# xduino360.net
KiCad netlist of a schematic drawn in EAGLE
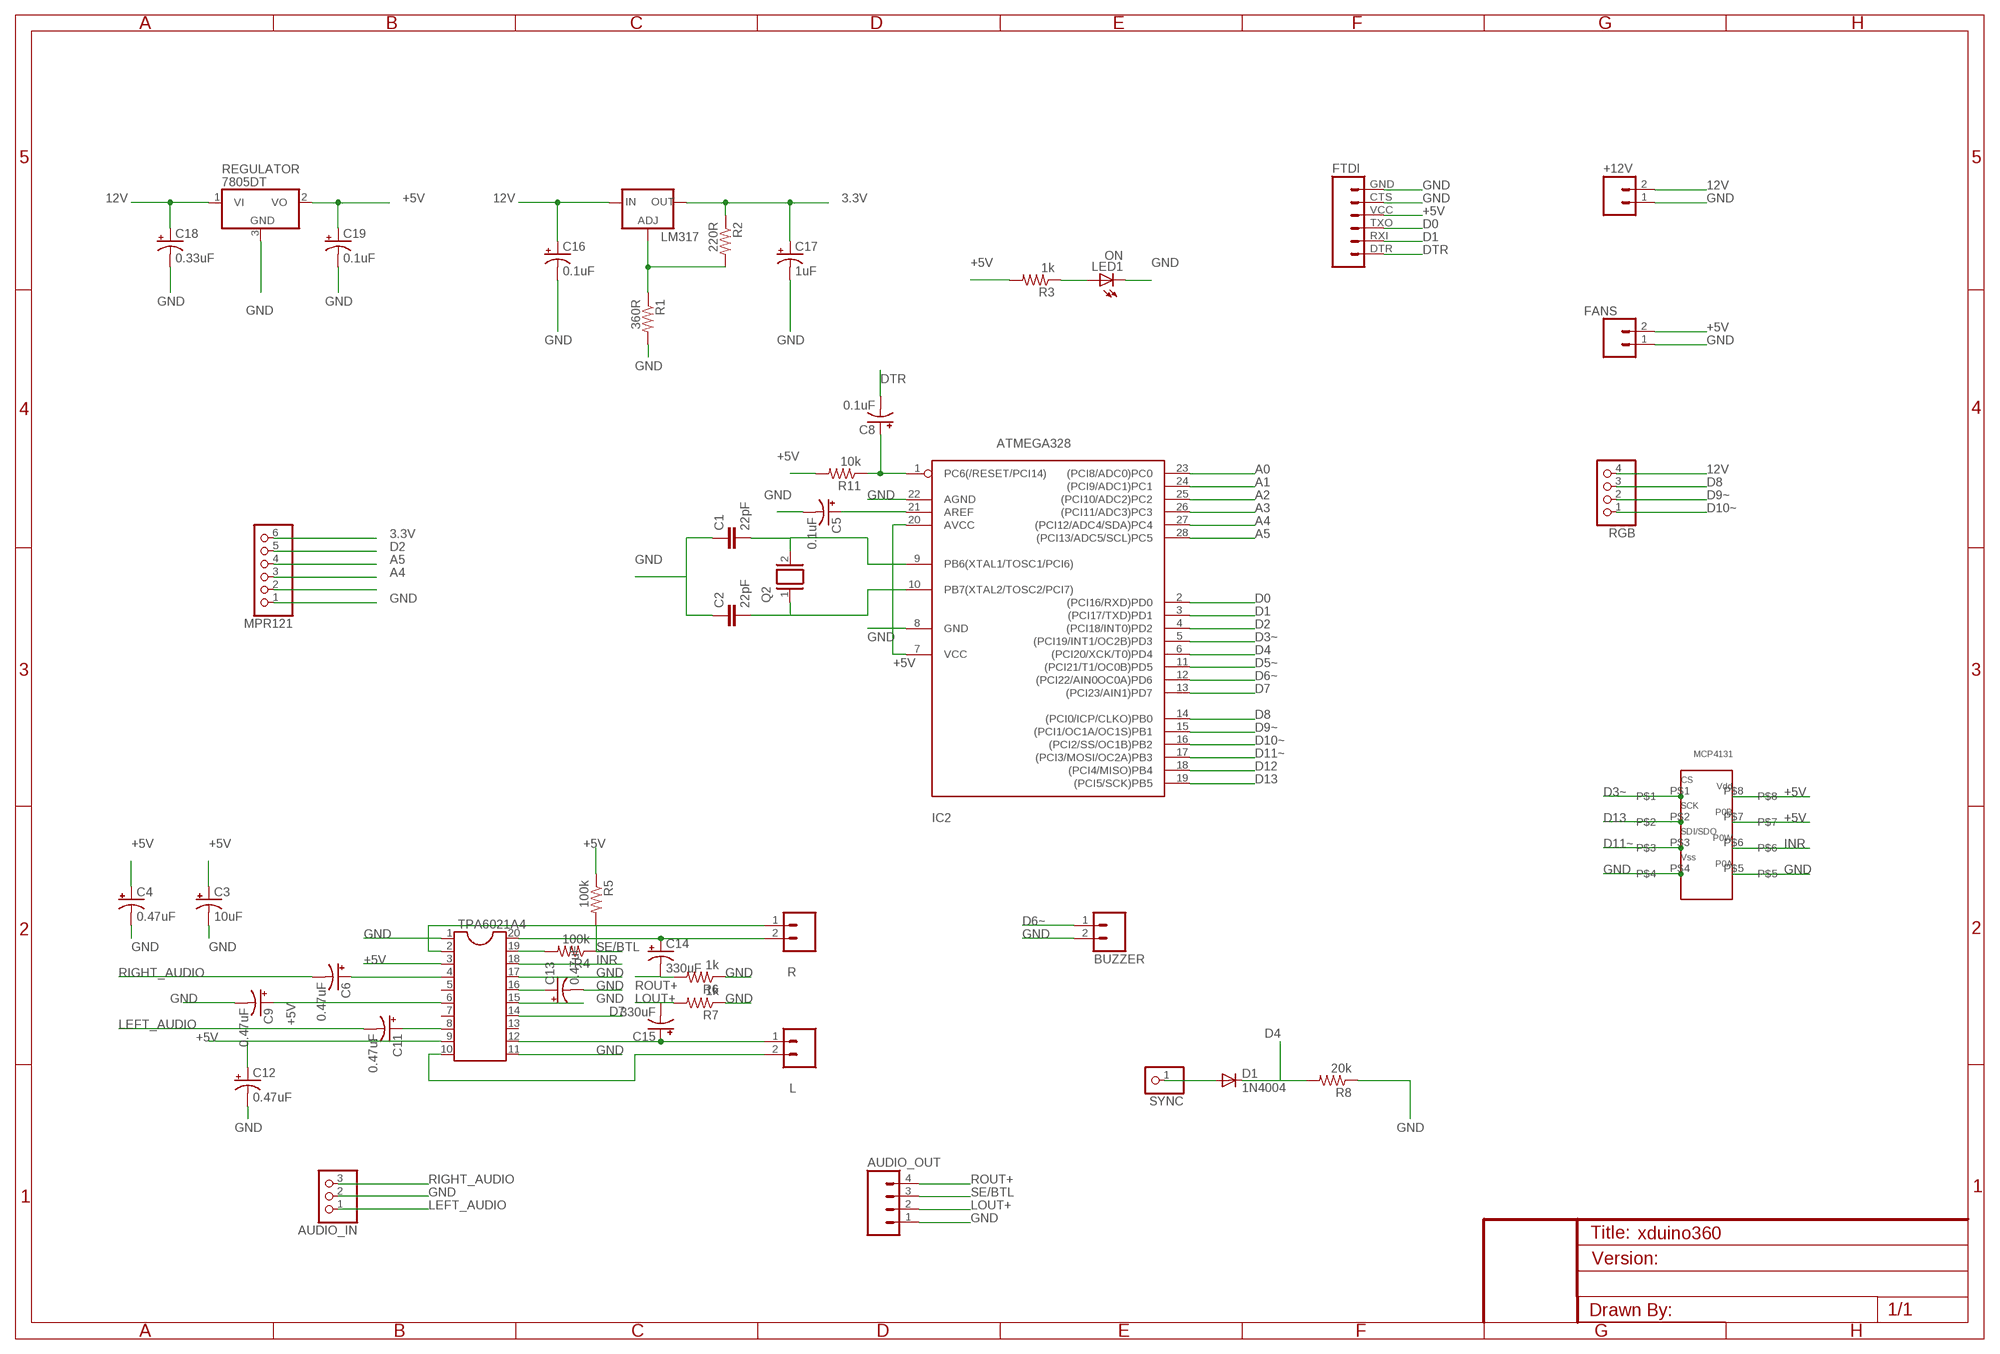
[diagram p0: schematic, sheet 1]

(export (version "E")
  (design (tool "Eeschema 10.0.6"))
  (components
    (comp (ref "+12V")
      (value "M02PTH")
      (footprint "eagle-import:1X02")
      (libsource (lib "eagle-import") (part "M02PTH"))
    )
    (comp (ref "AUDIO_IN")
      (value "PINHD-1X3")
      (footprint "eagle-import:1X03")
      (libsource (lib "eagle-import") (part "PINHD-1X3"))
    )
    (comp (ref "AUDIO_OUT")
      (value "M04PTH")
      (footprint "eagle-import:1X04")
      (libsource (lib "eagle-import") (part "M04PTH"))
    )
    (comp (ref "BUZZER")
      (value "M02PTH")
      (footprint "eagle-import:1X02")
      (libsource (lib "eagle-import") (part "M02PTH"))
    )
    (comp (ref "C1")
      (value "22pF")
      (footprint "eagle-import:C5B2.5")
      (libsource (lib "eagle-import") (part "C5/2.5"))
    )
    (comp (ref "C2")
      (value "22pF")
      (footprint "eagle-import:C5B2.5")
      (libsource (lib "eagle-import") (part "C5/2.5"))
    )
    (comp (ref "C3")
      (value "10uF")
      (footprint "eagle-import:TT2D5")
      (libsource (lib "eagle-import") (part "CPOL-USTT2D5"))
    )
    (comp (ref "C4")
      (value "0.47uF")
      (footprint "eagle-import:TT2D5")
      (libsource (lib "eagle-import") (part "CPOL-USTT2D5"))
    )
    (comp (ref "C5")
      (value "0.1uF")
      (footprint "eagle-import:TT2D5")
      (libsource (lib "eagle-import") (part "CPOL-USTT2D5"))
    )
    (comp (ref "C6")
      (value "0.47uF")
      (footprint "eagle-import:TT2D5")
      (libsource (lib "eagle-import") (part "CPOL-USTT2D5"))
    )
    (comp (ref "C8")
      (value "0.1uF")
      (footprint "eagle-import:TT2D5")
      (libsource (lib "eagle-import") (part "CPOL-USTT2D5"))
    )
    (comp (ref "C9")
      (value "0.47uF")
      (footprint "eagle-import:TT2D5")
      (libsource (lib "eagle-import") (part "CPOL-USTT2D5"))
    )
    (comp (ref "C11")
      (value "0.47uF")
      (footprint "eagle-import:TT2D5")
      (libsource (lib "eagle-import") (part "CPOL-USTT2D5"))
    )
    (comp (ref "C12")
      (value "0.47uF")
      (footprint "eagle-import:TT2D5")
      (libsource (lib "eagle-import") (part "CPOL-USTT2D5"))
    )
    (comp (ref "C13")
      (value "0.47uF")
      (footprint "eagle-import:TT2D5")
      (libsource (lib "eagle-import") (part "CPOL-USTT2D5"))
    )
    (comp (ref "C14")
      (value "330uF")
      (footprint "eagle-import:TT2D5")
      (libsource (lib "eagle-import") (part "CPOL-USTT2D5"))
    )
    (comp (ref "C15")
      (value "330uF")
      (footprint "eagle-import:TT2D5")
      (libsource (lib "eagle-import") (part "CPOL-USTT2D5"))
    )
    (comp (ref "C16")
      (value "0.1uF")
      (footprint "eagle-import:TT2D5")
      (libsource (lib "eagle-import") (part "CPOL-USTT2D5"))
    )
    (comp (ref "C17")
      (value "1uF")
      (footprint "eagle-import:TT2D5")
      (libsource (lib "eagle-import") (part "CPOL-USTT2D5"))
    )
    (comp (ref "C18")
      (value "0.33uF")
      (footprint "eagle-import:TT2D5")
      (libsource (lib "eagle-import") (part "CPOL-USTT2D5"))
    )
    (comp (ref "C19")
      (value "0.1uF")
      (footprint "eagle-import:TT2D5")
      (libsource (lib "eagle-import") (part "CPOL-USTT2D5"))
    )
    (comp (ref "D1")
      (value "1N4004")
      (footprint "eagle-import:DO41-10")
      (libsource (lib "eagle-import") (part "1N4004"))
    )
    (comp (ref "FANS")
      (value "M02PTH")
      (footprint "eagle-import:1X02")
      (libsource (lib "eagle-import") (part "M02PTH"))
    )
    (comp (ref "FTDI")
      (value "FTDI_BASICPTH")
      (footprint "eagle-import:FTDI_BASIC")
      (libsource (lib "eagle-import") (part "FTDI_BASICPTH"))
    )
    (comp (ref "IC2")
      (value "ATMEGA328")
      (footprint "eagle-import:DIL28-3")
      (libsource (lib "eagle-import") (part "ATMEGA168PV-10"))
    )
    (comp (ref "L")
      (value "M02PTH")
      (footprint "eagle-import:1X02")
      (libsource (lib "eagle-import") (part "M02PTH"))
    )
    (comp (ref "LED1")
      (value "ON")
      (footprint "eagle-import:LED3MM")
      (libsource (lib "eagle-import") (part "LED3MM"))
    )
    (comp (ref "LM317")
      (value "V_REG_317DPACK")
      (footprint "eagle-import:V-REG_DPACK")
      (libsource (lib "eagle-import") (part "V_REG_317DPACK"))
    )
    (comp (ref "MCP4131")
      (value "MCP4131")
      (footprint "eagle-import:MCP4131")
      (libsource (lib "eagle-import") (part "MCP4131"))
    )
    (comp (ref "MPR121")
      (value "PINHD-1X6")
      (footprint "eagle-import:1X06")
      (libsource (lib "eagle-import") (part "PINHD-1X6"))
    )
    (comp (ref "Q2")
      (value "XTAL/S")
      (footprint "eagle-import:QS")
      (libsource (lib "eagle-import") (part "XTAL/S"))
    )
    (comp (ref "R")
      (value "M02PTH")
      (footprint "eagle-import:1X02")
      (libsource (lib "eagle-import") (part "M02PTH"))
    )
    (comp (ref "R1")
      (value "360R")
      (footprint "eagle-import:0204V")
      (libsource (lib "eagle-import") (part "R-US_0204/2V"))
    )
    (comp (ref "R2")
      (value "220R")
      (footprint "eagle-import:0204V")
      (libsource (lib "eagle-import") (part "R-US_0204/2V"))
    )
    (comp (ref "R3")
      (value "1k")
      (footprint "eagle-import:0204V")
      (libsource (lib "eagle-import") (part "R-US_0204/2V"))
    )
    (comp (ref "R4")
      (value "100k")
      (footprint "eagle-import:0204V")
      (libsource (lib "eagle-import") (part "R-US_0204/2V"))
    )
    (comp (ref "R5")
      (value "100k")
      (footprint "eagle-import:0204V")
      (libsource (lib "eagle-import") (part "R-US_0204/2V"))
    )
    (comp (ref "R6")
      (value "1k")
      (footprint "eagle-import:0204V")
      (libsource (lib "eagle-import") (part "R-US_0204/2V"))
    )
    (comp (ref "R7")
      (value "1k")
      (footprint "eagle-import:0204V")
      (libsource (lib "eagle-import") (part "R-US_0204/2V"))
    )
    (comp (ref "R8")
      (value "20k")
      (footprint "eagle-import:0204V")
      (libsource (lib "eagle-import") (part "R-US_0204/2V"))
    )
    (comp (ref "R11")
      (value "10k")
      (footprint "eagle-import:0204V")
      (libsource (lib "eagle-import") (part "R-US_0204/2V"))
    )
    (comp (ref "REGULATOR")
      (value "7805DT")
      (footprint "eagle-import:TO252")
      (libsource (lib "eagle-import") (part "78DT05"))
    )
    (comp (ref "RGB")
      (value "PINHD-1X4")
      (footprint "eagle-import:1X04")
      (libsource (lib "eagle-import") (part "PINHD-1X4"))
    )
    (comp (ref "SYNC")
      (value "PINHD-1X1")
      (footprint "eagle-import:1X01")
      (libsource (lib "eagle-import") (part "PINHD-1X1"))
    )
    (comp (ref "TPA6021A4")
      (value "DIL20")
      (footprint "eagle-import:DIL20")
      (libsource (lib "eagle-import") (part "DIL20"))
    )
  )
  (nets
    (net (code "1") (name "/+5V") (class "Default")
      (node (ref "C12") (pin "+") (pinfunction "+_+") (pintype "passive"))
      (node (ref "C19") (pin "+") (pinfunction "+_+") (pintype "passive"))
      (node (ref "C3") (pin "+") (pinfunction "+_+") (pintype "passive"))
      (node (ref "C4") (pin "+") (pinfunction "+_+") (pintype "passive"))
      (node (ref "C9") (pin "+") (pinfunction "+_+") (pintype "passive"))
      (node (ref "FANS") (pin "2") (pinfunction "2_2") (pintype "passive"))
      (node (ref "FTDI") (pin "VCC") (pinfunction "4_VCC") (pintype "passive"))
      (node (ref "IC2") (pin "20") (pinfunction "AVCC_20") (pintype "bidirectional"))
      (node (ref "IC2") (pin "7") (pinfunction "VCC_7") (pintype "bidirectional"))
      (node (ref "MCP4131") (pin "P$7") (pinfunction "P$7_P$7") (pintype "bidirectional"))
      (node (ref "MCP4131") (pin "P$8") (pinfunction "P$8_P$8") (pintype "bidirectional"))
      (node (ref "R11") (pin "2") (pinfunction "2_2") (pintype "passive"))
      (node (ref "R3") (pin "2") (pinfunction "2_2") (pintype "passive"))
      (node (ref "R5") (pin "1") (pinfunction "1_1") (pintype "passive"))
      (node (ref "REGULATOR") (pin "2") (pinfunction "VO_2") (pintype "passive"))
      (node (ref "TPA6021A4") (pin "3") (pinfunction "3_3") (pintype "passive"))
      (node (ref "TPA6021A4") (pin "6") (pinfunction "6_6") (pintype "passive"))
      (node (ref "TPA6021A4") (pin "9") (pinfunction "9_9") (pintype "passive"))
    )
    (net (code "2") (name "/3.3V") (class "Default")
      (node (ref "C17") (pin "+") (pinfunction "+_+") (pintype "passive"))
      (node (ref "LM317") (pin "4") (pinfunction "OUT_4") (pintype "output"))
      (node (ref "MPR121") (pin "6") (pinfunction "6_6") (pintype "passive"))
      (node (ref "R2") (pin "1") (pinfunction "1_1") (pintype "passive"))
    )
    (net (code "3") (name "/12V") (class "Default")
      (node (ref "+12V") (pin "2") (pinfunction "2_2") (pintype "passive"))
      (node (ref "C16") (pin "+") (pinfunction "+_+") (pintype "passive"))
      (node (ref "C18") (pin "+") (pinfunction "+_+") (pintype "passive"))
      (node (ref "LM317") (pin "3") (pinfunction "IN_3") (pintype "input"))
      (node (ref "REGULATOR") (pin "1") (pinfunction "VI_1") (pintype "input"))
      (node (ref "RGB") (pin "4") (pinfunction "4_4") (pintype "passive"))
    )
    (net (code "4") (name "/A0") (class "Default")
      (node (ref "IC2") (pin "23") (pinfunction "(PCI8/ADC0)PC0_23") (pintype "bidirectional"))
    )
    (net (code "5") (name "/A1") (class "Default")
      (node (ref "IC2") (pin "24") (pinfunction "(PCI9/ADC1)PC1_24") (pintype "bidirectional"))
    )
    (net (code "6") (name "/A2") (class "Default")
      (node (ref "IC2") (pin "25") (pinfunction "(PCI10/ADC2)PC2_25") (pintype "bidirectional"))
    )
    (net (code "7") (name "/A3") (class "Default")
      (node (ref "IC2") (pin "26") (pinfunction "(PCI11/ADC3)PC3_26") (pintype "bidirectional"))
    )
    (net (code "8") (name "/A4") (class "Default")
      (node (ref "IC2") (pin "27") (pinfunction "(PCI12/ADC4/SDA)PC4_27") (pintype "bidirectional"))
      (node (ref "MPR121") (pin "3") (pinfunction "3_3") (pintype "passive"))
    )
    (net (code "9") (name "/A5") (class "Default")
      (node (ref "IC2") (pin "28") (pinfunction "(PCI13/ADC5/SCL)PC5_28") (pintype "bidirectional"))
      (node (ref "MPR121") (pin "4") (pinfunction "4_4") (pintype "passive"))
    )
    (net (code "10") (name "/D0") (class "Default")
      (node (ref "FTDI") (pin "TXO") (pinfunction "3_TXO") (pintype "passive"))
      (node (ref "IC2") (pin "2") (pinfunction "(PCI16/RXD)PD0_2") (pintype "bidirectional"))
    )
    (net (code "11") (name "/D1") (class "Default")
      (node (ref "FTDI") (pin "RXI") (pinfunction "2_RXI") (pintype "passive"))
      (node (ref "IC2") (pin "3") (pinfunction "(PCI17/TXD)PD1_3") (pintype "bidirectional"))
    )
    (net (code "12") (name "/D2") (class "Default")
      (node (ref "IC2") (pin "4") (pinfunction "(PCI18/INT0)PD2_4") (pintype "bidirectional"))
      (node (ref "MPR121") (pin "5") (pinfunction "5_5") (pintype "passive"))
    )
    (net (code "13") (name "/D3~{}") (class "Default")
      (node (ref "IC2") (pin "5") (pinfunction "(PCI19/INT1/OC2B)PD3_5") (pintype "bidirectional"))
      (node (ref "MCP4131") (pin "P$1") (pinfunction "P$1_P$1") (pintype "bidirectional"))
    )
    (net (code "14") (name "/D4") (class "Default")
      (node (ref "D1") (pin "C") (pinfunction "C_C") (pintype "passive"))
      (node (ref "IC2") (pin "6") (pinfunction "(PCI20/XCK/T0)PD4_6") (pintype "bidirectional"))
      (node (ref "R8") (pin "2") (pinfunction "2_2") (pintype "passive"))
    )
    (net (code "15") (name "/D5~{}") (class "Default")
      (node (ref "IC2") (pin "11") (pinfunction "(PCI21/T1/OC0B)PD5_11") (pintype "bidirectional"))
    )
    (net (code "16") (name "/D6~{}") (class "Default")
      (node (ref "BUZZER") (pin "1") (pinfunction "1_1") (pintype "passive"))
      (node (ref "IC2") (pin "12") (pinfunction "(PCI22/AIN0OC0A)PD6_12") (pintype "bidirectional"))
    )
    (net (code "17") (name "/D7") (class "Default")
      (node (ref "IC2") (pin "13") (pinfunction "(PCI23/AIN1)PD7_13") (pintype "bidirectional"))
      (node (ref "TPA6021A4") (pin "14") (pinfunction "14_14") (pintype "passive"))
    )
    (net (code "18") (name "/D8") (class "Default")
      (node (ref "IC2") (pin "14") (pinfunction "(PCI0/ICP/CLKO)PB0_14") (pintype "bidirectional"))
      (node (ref "RGB") (pin "3") (pinfunction "3_3") (pintype "passive"))
    )
    (net (code "19") (name "/D9~{}") (class "Default")
      (node (ref "IC2") (pin "15") (pinfunction "(PCI1/OC1A/OC1S)PB1_15") (pintype "bidirectional"))
      (node (ref "RGB") (pin "2") (pinfunction "2_2") (pintype "passive"))
    )
    (net (code "20") (name "/D10~{}") (class "Default")
      (node (ref "IC2") (pin "16") (pinfunction "(PCI2/SS/OC1B)PB2_16") (pintype "bidirectional"))
      (node (ref "RGB") (pin "1") (pinfunction "1_1") (pintype "passive"))
    )
    (net (code "21") (name "/D11~{}") (class "Default")
      (node (ref "IC2") (pin "17") (pinfunction "(PCI3/MOSI/OC2A)PB3_17") (pintype "bidirectional"))
      (node (ref "MCP4131") (pin "P$3") (pinfunction "P$3_P$3") (pintype "bidirectional"))
    )
    (net (code "22") (name "/D12") (class "Default")
      (node (ref "IC2") (pin "18") (pinfunction "(PCI4/MISO)PB4_18") (pintype "bidirectional"))
    )
    (net (code "23") (name "/D13") (class "Default")
      (node (ref "IC2") (pin "19") (pinfunction "(PCI5/SCK)PB5_19") (pintype "bidirectional"))
      (node (ref "MCP4131") (pin "P$2") (pinfunction "P$2_P$2") (pintype "bidirectional"))
    )
    (net (code "24") (name "/DTR") (class "Default")
      (node (ref "C8") (pin "-") (pinfunction "-_-") (pintype "passive"))
      (node (ref "FTDI") (pin "DTR") (pinfunction "1_DTR") (pintype "passive"))
    )
    (net (code "25") (name "/GND") (class "Default")
      (node (ref "+12V") (pin "1") (pinfunction "1_1") (pintype "passive"))
      (node (ref "AUDIO_IN") (pin "2") (pinfunction "2_2") (pintype "passive"))
      (node (ref "AUDIO_OUT") (pin "1") (pinfunction "1_1") (pintype "passive"))
      (node (ref "BUZZER") (pin "2") (pinfunction "2_2") (pintype "passive"))
      (node (ref "C1") (pin "1") (pinfunction "1_1") (pintype "passive"))
      (node (ref "C12") (pin "-") (pinfunction "-_-") (pintype "passive"))
      (node (ref "C13") (pin "-") (pinfunction "-_-") (pintype "passive"))
      (node (ref "C16") (pin "-") (pinfunction "-_-") (pintype "passive"))
      (node (ref "C17") (pin "-") (pinfunction "-_-") (pintype "passive"))
      (node (ref "C18") (pin "-") (pinfunction "-_-") (pintype "passive"))
      (node (ref "C19") (pin "-") (pinfunction "-_-") (pintype "passive"))
      (node (ref "C2") (pin "1") (pinfunction "1_1") (pintype "passive"))
      (node (ref "C3") (pin "-") (pinfunction "-_-") (pintype "passive"))
      (node (ref "C4") (pin "-") (pinfunction "-_-") (pintype "passive"))
      (node (ref "C5") (pin "-") (pinfunction "-_-") (pintype "passive"))
      (node (ref "C9") (pin "-") (pinfunction "-_-") (pintype "passive"))
      (node (ref "FANS") (pin "1") (pinfunction "1_1") (pintype "passive"))
      (node (ref "FTDI") (pin "CTS") (pinfunction "5_CTS") (pintype "passive"))
      (node (ref "FTDI") (pin "GND") (pinfunction "6_GND") (pintype "passive"))
      (node (ref "IC2") (pin "22") (pinfunction "AGND_22") (pintype "bidirectional"))
      (node (ref "IC2") (pin "8") (pinfunction "GND_8") (pintype "bidirectional"))
      (node (ref "LED1") (pin "K") (pinfunction "C_K") (pintype "passive"))
      (node (ref "MCP4131") (pin "P$4") (pinfunction "P$4_P$4") (pintype "bidirectional"))
      (node (ref "MCP4131") (pin "P$5") (pinfunction "P$5_P$5") (pintype "bidirectional"))
      (node (ref "MPR121") (pin "1") (pinfunction "1_1") (pintype "passive"))
      (node (ref "R1") (pin "2") (pinfunction "2_2") (pintype "passive"))
      (node (ref "R6") (pin "1") (pinfunction "1_1") (pintype "passive"))
      (node (ref "R7") (pin "1") (pinfunction "1_1") (pintype "passive"))
      (node (ref "R8") (pin "1") (pinfunction "1_1") (pintype "passive"))
      (node (ref "REGULATOR") (pin "3") (pinfunction "GND_3") (pintype "passive"))
      (node (ref "TPA6021A4") (pin "1") (pinfunction "1_1") (pintype "passive"))
      (node (ref "TPA6021A4") (pin "11") (pinfunction "11_11") (pintype "passive"))
      (node (ref "TPA6021A4") (pin "15") (pinfunction "15_15") (pintype "passive"))
      (node (ref "TPA6021A4") (pin "17") (pinfunction "17_17") (pintype "passive"))
    )
    (net (code "26") (name "/INR") (class "Default")
      (node (ref "MCP4131") (pin "P$6") (pinfunction "P$6_P$6") (pintype "bidirectional"))
      (node (ref "TPA6021A4") (pin "18") (pinfunction "18_18") (pintype "passive"))
    )
    (net (code "27") (name "/LEFT_AUDIO") (class "Default")
      (node (ref "AUDIO_IN") (pin "1") (pinfunction "1_1") (pintype "passive"))
      (node (ref "C11") (pin "-") (pinfunction "-_-") (pintype "passive"))
    )
    (net (code "28") (name "/LOUT+") (class "Default")
      (node (ref "AUDIO_OUT") (pin "2") (pinfunction "2_2") (pintype "passive"))
      (node (ref "C15") (pin "-") (pinfunction "-_-") (pintype "passive"))
      (node (ref "R7") (pin "2") (pinfunction "2_2") (pintype "passive"))
    )
    (net (code "29") (name "/RIGHT_AUDIO") (class "Default")
      (node (ref "AUDIO_IN") (pin "3") (pinfunction "3_3") (pintype "passive"))
      (node (ref "C6") (pin "-") (pinfunction "-_-") (pintype "passive"))
    )
    (net (code "30") (name "/ROUT+") (class "Default")
      (node (ref "AUDIO_OUT") (pin "4") (pinfunction "4_4") (pintype "passive"))
      (node (ref "C14") (pin "-") (pinfunction "-_-") (pintype "passive"))
      (node (ref "R6") (pin "2") (pinfunction "2_2") (pintype "passive"))
    )
    (net (code "31") (name "/SE{slash}BTL") (class "Default")
      (node (ref "AUDIO_OUT") (pin "3") (pinfunction "3_3") (pintype "passive"))
      (node (ref "R4") (pin "1") (pinfunction "1_1") (pintype "passive"))
      (node (ref "R5") (pin "2") (pinfunction "2_2") (pintype "passive"))
    )
    (net (code "32") (name "Net-(C6-Pad+)") (class "Default")
      (node (ref "C6") (pin "+") (pinfunction "+_+") (pintype "passive"))
      (node (ref "TPA6021A4") (pin "4") (pinfunction "4_4") (pintype "passive"))
    )
    (net (code "33") (name "Net-(C11-Pad+)") (class "Default")
      (node (ref "C11") (pin "+") (pinfunction "+_+") (pintype "passive"))
      (node (ref "TPA6021A4") (pin "8") (pinfunction "8_8") (pintype "passive"))
    )
    (net (code "34") (name "Net-(C13-Pad+)") (class "Default")
      (node (ref "C13") (pin "+") (pinfunction "+_+") (pintype "passive"))
      (node (ref "TPA6021A4") (pin "16") (pinfunction "16_16") (pintype "passive"))
    )
    (net (code "35") (name "Net-(C14-Pad+)") (class "Default")
      (node (ref "C14") (pin "+") (pinfunction "+_+") (pintype "passive"))
      (node (ref "R") (pin "2") (pinfunction "2_2") (pintype "passive"))
      (node (ref "TPA6021A4") (pin "20") (pinfunction "20_20") (pintype "passive"))
    )
    (net (code "36") (name "Net-(C15-Pad+)") (class "Default")
      (node (ref "C15") (pin "+") (pinfunction "+_+") (pintype "passive"))
      (node (ref "L") (pin "1") (pinfunction "1_1") (pintype "passive"))
      (node (ref "TPA6021A4") (pin "12") (pinfunction "12_12") (pintype "passive"))
    )
    (net (code "37") (name "Net-(D1-PadA)") (class "Default")
      (node (ref "D1") (pin "A") (pinfunction "A_A") (pintype "passive"))
      (node (ref "SYNC") (pin "1") (pinfunction "1_1") (pintype "passive"))
    )
    (net (code "38") (name "Net-(IC2-AREF)") (class "Default")
      (node (ref "C5") (pin "+") (pinfunction "+_+") (pintype "passive"))
      (node (ref "IC2") (pin "21") (pinfunction "AREF_21") (pintype "bidirectional"))
    )
    (net (code "39") (name "Net-(IC2-PB6(XTAL1{slash}TOSC1{slash}PCI6))") (class "Default")
      (node (ref "C1") (pin "2") (pinfunction "2_2") (pintype "passive"))
      (node (ref "IC2") (pin "9") (pinfunction "PB6(XTAL1/TOSC1/PCI6)_9") (pintype "bidirectional"))
      (node (ref "Q2") (pin "2") (pinfunction "2_2") (pintype "passive"))
    )
    (net (code "40") (name "Net-(IC2-PB7(XTAL2{slash}TOSC2{slash}PCI7))") (class "Default")
      (node (ref "C2") (pin "2") (pinfunction "2_2") (pintype "passive"))
      (node (ref "IC2") (pin "10") (pinfunction "PB7(XTAL2/TOSC2/PCI7)_10") (pintype "bidirectional"))
      (node (ref "Q2") (pin "1") (pinfunction "1_1") (pintype "passive"))
    )
    (net (code "41") (name "Net-(IC2-PC6({slash}RESET{slash}PCI14))") (class "Default")
      (node (ref "C8") (pin "+") (pinfunction "+_+") (pintype "passive"))
      (node (ref "IC2") (pin "1") (pinfunction "PC6(/RESET/PCI14)_1") (pintype "bidirectional"))
      (node (ref "R11") (pin "1") (pinfunction "1_1") (pintype "passive"))
    )
    (net (code "42") (name "Net-(L-Pad2)") (class "Default")
      (node (ref "L") (pin "2") (pinfunction "2_2") (pintype "passive"))
      (node (ref "TPA6021A4") (pin "10") (pinfunction "10_10") (pintype "passive"))
    )
    (net (code "43") (name "Net-(LED1-PadA)") (class "Default")
      (node (ref "LED1") (pin "A") (pinfunction "A_A") (pintype "passive"))
      (node (ref "R3") (pin "1") (pinfunction "1_1") (pintype "passive"))
    )
    (net (code "44") (name "Net-(LM317-ADJ)") (class "Default")
      (node (ref "LM317") (pin "1") (pinfunction "ADJ_1") (pintype "input"))
      (node (ref "R1") (pin "1") (pinfunction "1_1") (pintype "passive"))
      (node (ref "R2") (pin "2") (pinfunction "2_2") (pintype "passive"))
    )
    (net (code "45") (name "Net-(R-Pad1)") (class "Default")
      (node (ref "R") (pin "1") (pinfunction "1_1") (pintype "passive"))
      (node (ref "TPA6021A4") (pin "2") (pinfunction "2_2") (pintype "passive"))
    )
    (net (code "46") (name "Net-(R4-Pad2)") (class "Default")
      (node (ref "R4") (pin "2") (pinfunction "2_2") (pintype "passive"))
      (node (ref "TPA6021A4") (pin "19") (pinfunction "19_19") (pintype "passive"))
    )
    (net (code "47") (name "unconnected-(MPR121-Pad2)") (class "Default")
      (node (ref "MPR121") (pin "2") (pinfunction "2_2") (pintype "passive"))
    )
    (net (code "48") (name "unconnected-(TPA6021A4-Pad5)") (class "Default")
      (node (ref "TPA6021A4") (pin "5") (pinfunction "5_5") (pintype "passive"))
    )
    (net (code "49") (name "unconnected-(TPA6021A4-Pad7)") (class "Default")
      (node (ref "TPA6021A4") (pin "7") (pinfunction "7_7") (pintype "passive"))
    )
    (net (code "50") (name "unconnected-(TPA6021A4-Pad13)") (class "Default")
      (node (ref "TPA6021A4") (pin "13") (pinfunction "13_13") (pintype "passive"))
    )
  )
)
